# Power_Circuit.net
KiCad netlist of a schematic drawn in Altium Designer
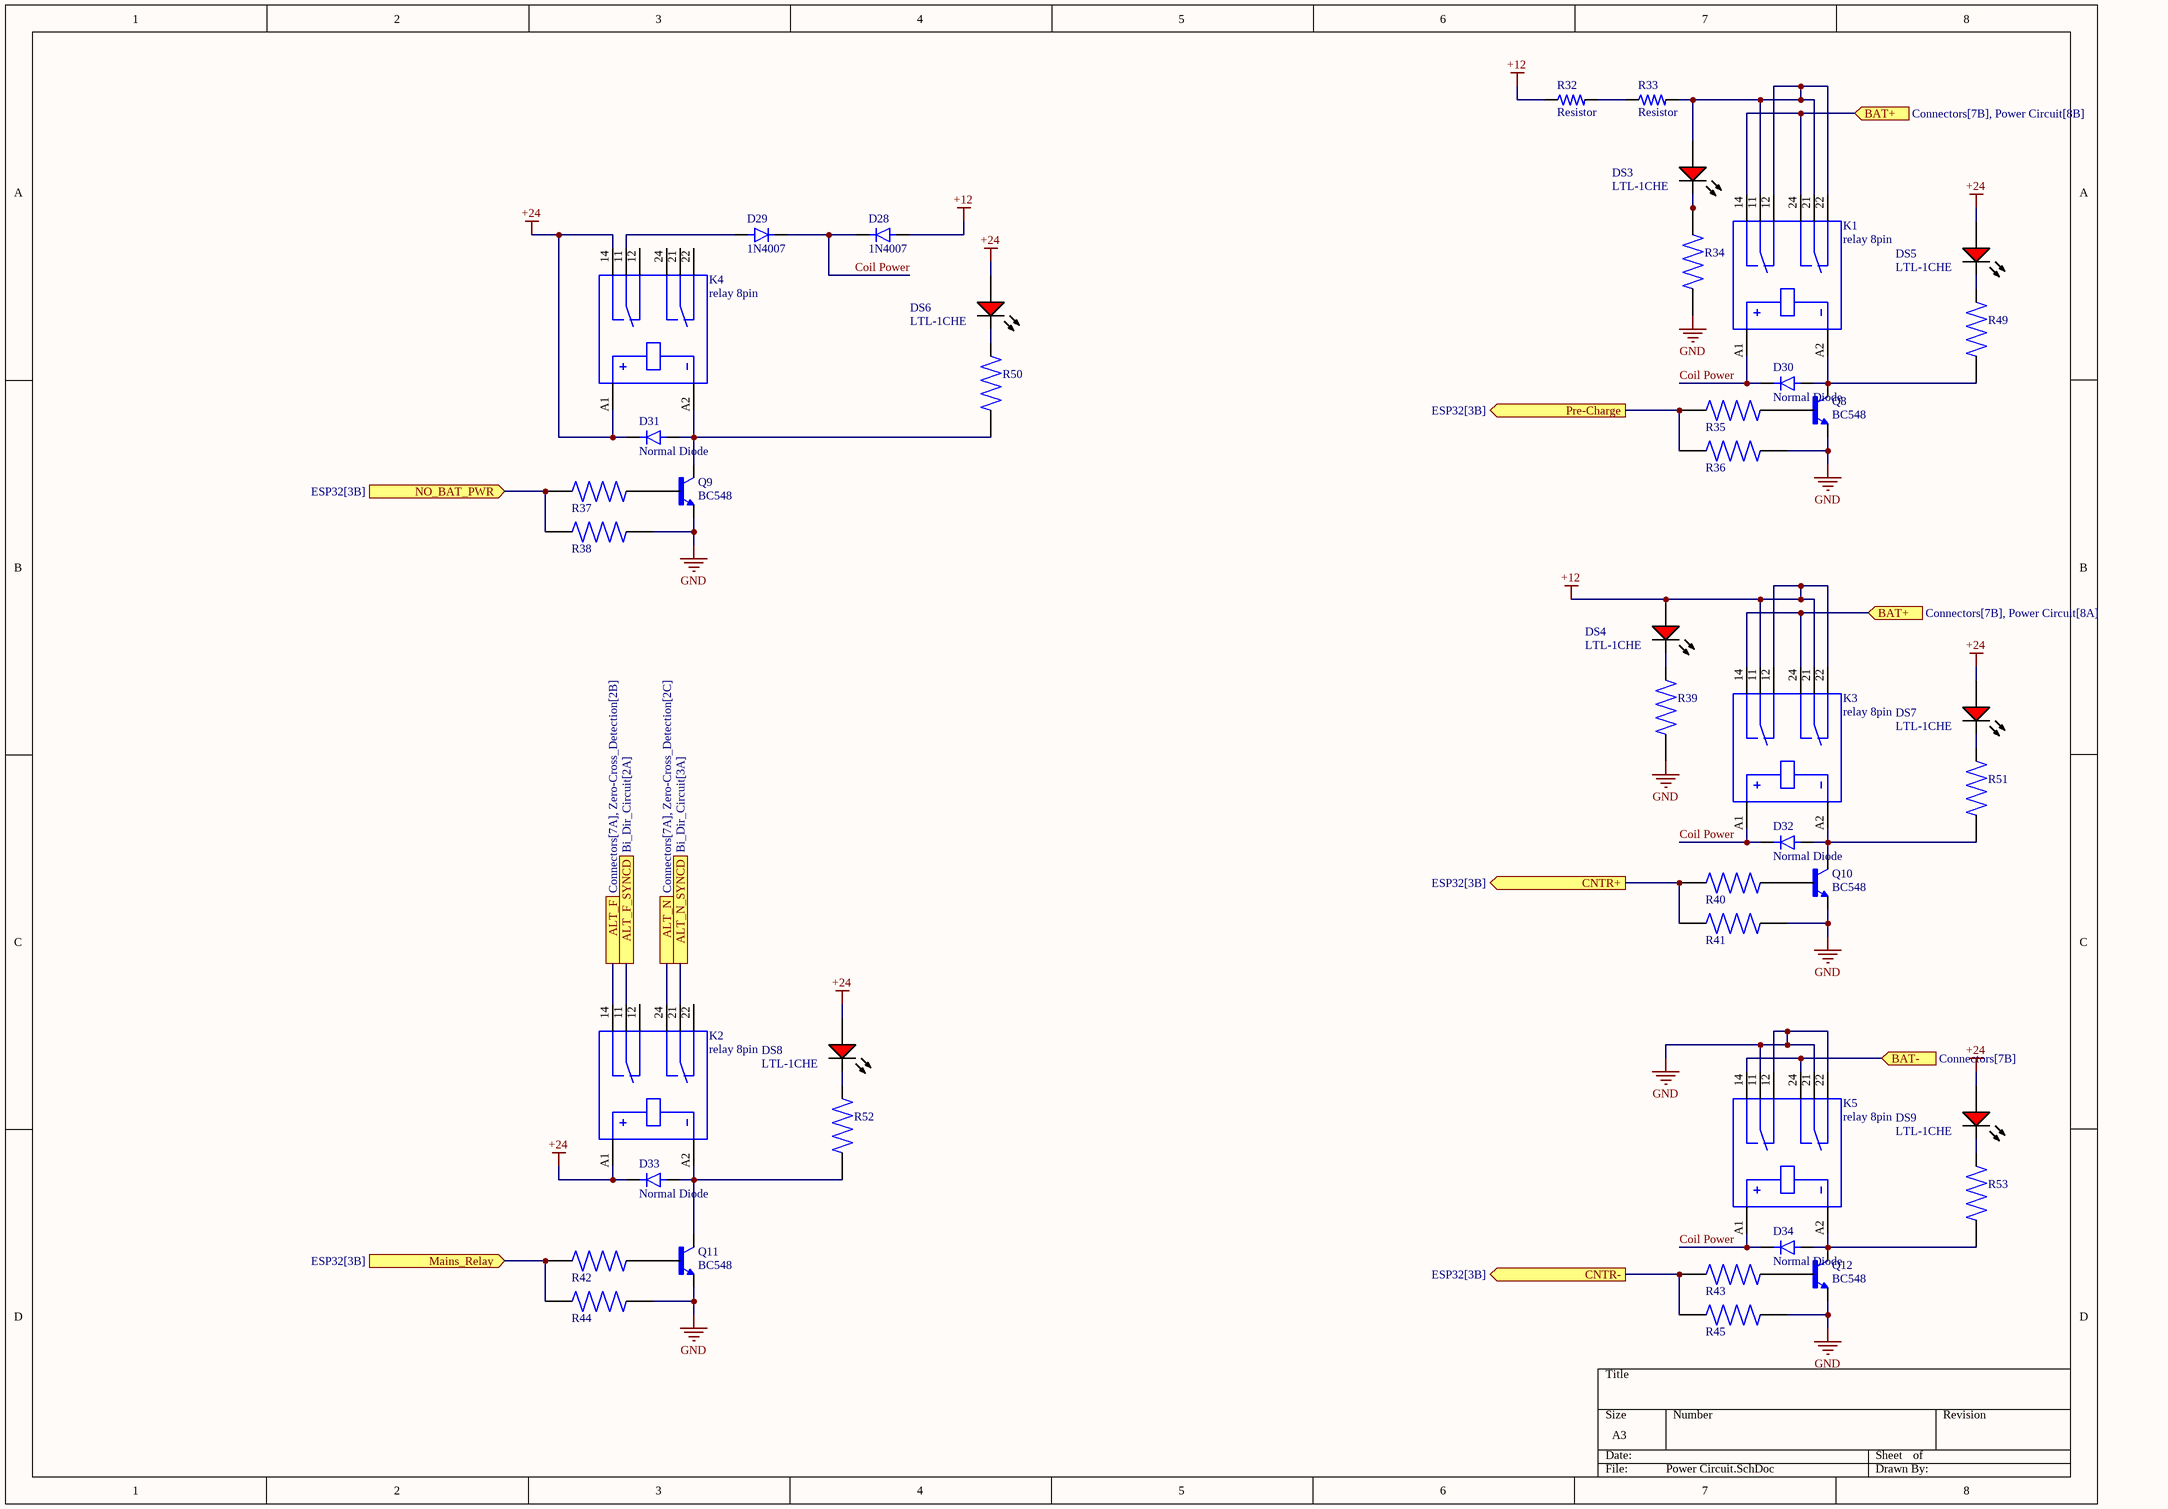
[diagram p0: Power Circuit.SchDoc]

(export (version "E")
  (design (tool "Eeschema 10.0.6"))
  (components
    (comp (ref "D28")
      (value "1N4007")
      (footprint "Common Trhough Hole")
      (fields (field (name "MF") "NTE Electronics, Inc."))
      (libsource (lib "Diodes Through Hole") (part "Normal Diode"))
    )
    (comp (ref "D29")
      (value "1N4007")
      (footprint "Common Trhough Hole")
      (fields (field (name "MF") "NTE Electronics, Inc."))
      (libsource (lib "Diodes Through Hole") (part "Normal Diode"))
    )
    (comp (ref "D30")
      (value "Normal Diode")
      (footprint "Common Trhough Hole")
      (fields (field (name "MF") "NTE Electronics, Inc.") (field (name "MP") "1N4007"))
      (libsource (lib "Diodes Through Hole") (part "Normal Diode"))
    )
    (comp (ref "D31")
      (value "Normal Diode")
      (footprint "Common Trhough Hole")
      (fields (field (name "MF") "NTE Electronics, Inc.") (field (name "MP") "1N4007"))
      (libsource (lib "Diodes Through Hole") (part "Normal Diode"))
    )
    (comp (ref "D32")
      (value "Normal Diode")
      (footprint "Common Trhough Hole")
      (fields (field (name "MF") "NTE Electronics, Inc.") (field (name "MP") "1N4007"))
      (libsource (lib "Diodes Through Hole") (part "Normal Diode"))
    )
    (comp (ref "D33")
      (value "Normal Diode")
      (footprint "Common Trhough Hole")
      (fields (field (name "MF") "NTE Electronics, Inc.") (field (name "MP") "1N4007"))
      (libsource (lib "Diodes Through Hole") (part "Normal Diode"))
    )
    (comp (ref "D34")
      (value "Normal Diode")
      (footprint "Common Trhough Hole")
      (fields (field (name "MF") "NTE Electronics, Inc.") (field (name "MP") "1N4007"))
      (libsource (lib "Diodes Through Hole") (part "Normal Diode"))
    )
    (comp (ref "DS3")
      (value "LTL-1CHE")
      (footprint "LED3mm")
      (description "Radial LED, 12.6 mcd, 20 mA, 2 V, -55 to 100 degC, 2-Pin THD, RoHS, Bulk")
      (fields (field (name "TOLERANCE") "20%"))
      (libsource (lib "MySCH_Library") (part "RED_LED 3mm"))
    )
    (comp (ref "DS4")
      (value "LTL-1CHE")
      (footprint "LED3mm")
      (description "Radial LED, 12.6 mcd, 20 mA, 2 V, -55 to 100 degC, 2-Pin THD, RoHS, Bulk")
      (fields (field (name "TOLERANCE") "20%"))
      (libsource (lib "MySCH_Library") (part "RED_LED 3mm"))
    )
    (comp (ref "DS5")
      (value "LTL-1CHE")
      (footprint "LED3mm")
      (description "Radial LED, 12.6 mcd, 20 mA, 2 V, -55 to 100 degC, 2-Pin THD, RoHS, Bulk")
      (fields (field (name "TOLERANCE") "20%"))
      (libsource (lib "MySCH_Library") (part "RED_LED 3mm"))
    )
    (comp (ref "DS6")
      (value "LTL-1CHE")
      (footprint "LED3mm")
      (description "Radial LED, 12.6 mcd, 20 mA, 2 V, -55 to 100 degC, 2-Pin THD, RoHS, Bulk")
      (fields (field (name "TOLERANCE") "20%"))
      (libsource (lib "MySCH_Library") (part "RED_LED 3mm"))
    )
    (comp (ref "DS7")
      (value "LTL-1CHE")
      (footprint "LED3mm")
      (description "Radial LED, 12.6 mcd, 20 mA, 2 V, -55 to 100 degC, 2-Pin THD, RoHS, Bulk")
      (fields (field (name "TOLERANCE") "20%"))
      (libsource (lib "MySCH_Library") (part "RED_LED 3mm"))
    )
    (comp (ref "DS8")
      (value "LTL-1CHE")
      (footprint "LED3mm")
      (description "Radial LED, 12.6 mcd, 20 mA, 2 V, -55 to 100 degC, 2-Pin THD, RoHS, Bulk")
      (fields (field (name "TOLERANCE") "20%"))
      (libsource (lib "MySCH_Library") (part "RED_LED 3mm"))
    )
    (comp (ref "DS9")
      (value "LTL-1CHE")
      (footprint "LED3mm")
      (description "Radial LED, 12.6 mcd, 20 mA, 2 V, -55 to 100 degC, 2-Pin THD, RoHS, Bulk")
      (fields (field (name "TOLERANCE") "20%"))
      (libsource (lib "MySCH_Library") (part "RED_LED 3mm"))
    )
    (comp (ref "K1")
      (value "relay 8pin")
      (footprint "Relay socket 8pin")
      (description "General Purpose Relay DPDT _2 Form C_ 24VDC Coil Through Hole")
      (fields (field (name "MF") "TE Connectivity") (field (name "MP") "1-1393243-0"))
      (libsource (lib "MySCH_Library") (part "relay 8pin"))
    )
    (comp (ref "K2")
      (value "relay 8pin")
      (footprint "Relay socket 8pin")
      (description "General Purpose Relay DPDT _2 Form C_ 24VDC Coil Through Hole")
      (fields (field (name "MF") "TE Connectivity") (field (name "MP") "1-1393243-0"))
      (libsource (lib "MySCH_Library") (part "relay 8pin"))
    )
    (comp (ref "K3")
      (value "relay 8pin")
      (footprint "Relay socket 8pin")
      (description "General Purpose Relay DPDT _2 Form C_ 24VDC Coil Through Hole")
      (fields (field (name "MF") "TE Connectivity") (field (name "MP") "1-1393243-0"))
      (libsource (lib "MySCH_Library") (part "relay 8pin"))
    )
    (comp (ref "K4")
      (value "relay 8pin")
      (footprint "Relay socket 8pin")
      (description "General Purpose Relay DPDT _2 Form C_ 24VDC Coil Through Hole")
      (fields (field (name "MF") "TE Connectivity") (field (name "MP") "1-1393243-0"))
      (libsource (lib "MySCH_Library") (part "relay 8pin"))
    )
    (comp (ref "K5")
      (value "relay 8pin")
      (footprint "Relay socket 8pin")
      (description "General Purpose Relay DPDT _2 Form C_ 24VDC Coil Through Hole")
      (fields (field (name "MF") "TE Connectivity") (field (name "MP") "1-1393243-0"))
      (libsource (lib "MySCH_Library") (part "relay 8pin"))
    )
    (comp (ref "Q8")
      (value "BC548")
      (footprint "bc548")
      (description "Bipolar (BJT) Transistor NPN 30V 100mA 300MHz 500mW Through Hole TO-92-3")
      (fields (field (name "MF") "ON Semiconductor"))
      (libsource (lib "MySCH_Library") (part "BC548"))
    )
    (comp (ref "Q9")
      (value "BC548")
      (footprint "bc548")
      (description "Bipolar (BJT) Transistor NPN 30V 100mA 300MHz 500mW Through Hole TO-92-3")
      (fields (field (name "MF") "ON Semiconductor"))
      (libsource (lib "MySCH_Library") (part "BC548"))
    )
    (comp (ref "Q10")
      (value "BC548")
      (footprint "bc548")
      (description "Bipolar (BJT) Transistor NPN 30V 100mA 300MHz 500mW Through Hole TO-92-3")
      (fields (field (name "MF") "ON Semiconductor"))
      (libsource (lib "MySCH_Library") (part "BC548"))
    )
    (comp (ref "Q11")
      (value "BC548")
      (footprint "bc548")
      (description "Bipolar (BJT) Transistor NPN 30V 100mA 300MHz 500mW Through Hole TO-92-3")
      (fields (field (name "MF") "ON Semiconductor"))
      (libsource (lib "MySCH_Library") (part "BC548"))
    )
    (comp (ref "Q12")
      (value "BC548")
      (footprint "bc548")
      (description "Bipolar (BJT) Transistor NPN 30V 100mA 300MHz 500mW Through Hole TO-92-3")
      (fields (field (name "MF") "ON Semiconductor"))
      (libsource (lib "MySCH_Library") (part "BC548"))
    )
    (comp (ref "R32")
      (value "Resistor")
      (footprint "Resistor_Through Hole")
      (fields
        (field (name "MP") "2-2176053-0")
        (field (name "TOLERANCE") "1%")
        (field (name "MF") "TE Connectivity")
      )
      (libsource (lib "Resistors Through Hole") (part "Resistor"))
    )
    (comp (ref "R33")
      (value "Resistor")
      (footprint "Resistor_Through Hole")
      (fields
        (field (name "MP") "2-2176053-0")
        (field (name "TOLERANCE") "1%")
        (field (name "MF") "TE Connectivity")
      )
      (libsource (lib "Resistors Through Hole") (part "Resistor"))
    )
    (comp (ref "R34")
      (value "Resistor_Through Hole")
      (footprint "Resistor_Through Hole")
      (description "1.02 Ohms Â±1% 0.25W, 1/4W Through Hole Resistor Axial Metal Film")
      (fields (field (name "MP") "MFR-25FTE52-1R") (field (name "MF") "Yageo"))
      (libsource (lib "MySCH_Library") (part "Resistor_Through Hole"))
    )
    (comp (ref "R35")
      (value "Resistor_Through Hole")
      (footprint "Resistor_Through Hole")
      (description "1.02 Ohms Â±1% 0.25W, 1/4W Through Hole Resistor Axial Metal Film")
      (fields (field (name "MP") "MFR-25FTE52-1R") (field (name "MF") "Yageo"))
      (libsource (lib "MySCH_Library") (part "Resistor_Through Hole"))
    )
    (comp (ref "R36")
      (value "Resistor_Through Hole")
      (footprint "Resistor_Through Hole")
      (description "1.02 Ohms Â±1% 0.25W, 1/4W Through Hole Resistor Axial Metal Film")
      (fields (field (name "MP") "MFR-25FTE52-1R") (field (name "MF") "Yageo"))
      (libsource (lib "MySCH_Library") (part "Resistor_Through Hole"))
    )
    (comp (ref "R37")
      (value "Resistor_Through Hole")
      (footprint "Resistor_Through Hole")
      (description "1.02 Ohms Â±1% 0.25W, 1/4W Through Hole Resistor Axial Metal Film")
      (fields (field (name "MP") "MFR-25FTE52-1R") (field (name "MF") "Yageo"))
      (libsource (lib "MySCH_Library") (part "Resistor_Through Hole"))
    )
    (comp (ref "R38")
      (value "Resistor_Through Hole")
      (footprint "Resistor_Through Hole")
      (description "1.02 Ohms Â±1% 0.25W, 1/4W Through Hole Resistor Axial Metal Film")
      (fields (field (name "MP") "MFR-25FTE52-1R") (field (name "MF") "Yageo"))
      (libsource (lib "MySCH_Library") (part "Resistor_Through Hole"))
    )
    (comp (ref "R39")
      (value "Resistor_Through Hole")
      (footprint "Resistor_Through Hole")
      (description "1.02 Ohms Â±1% 0.25W, 1/4W Through Hole Resistor Axial Metal Film")
      (fields (field (name "MP") "MFR-25FTE52-1R") (field (name "MF") "Yageo"))
      (libsource (lib "MySCH_Library") (part "Resistor_Through Hole"))
    )
    (comp (ref "R40")
      (value "Resistor_Through Hole")
      (footprint "Resistor_Through Hole")
      (description "1.02 Ohms Â±1% 0.25W, 1/4W Through Hole Resistor Axial Metal Film")
      (fields (field (name "MP") "MFR-25FTE52-1R") (field (name "MF") "Yageo"))
      (libsource (lib "MySCH_Library") (part "Resistor_Through Hole"))
    )
    (comp (ref "R41")
      (value "Resistor_Through Hole")
      (footprint "Resistor_Through Hole")
      (description "1.02 Ohms Â±1% 0.25W, 1/4W Through Hole Resistor Axial Metal Film")
      (fields (field (name "MP") "MFR-25FTE52-1R") (field (name "MF") "Yageo"))
      (libsource (lib "MySCH_Library") (part "Resistor_Through Hole"))
    )
    (comp (ref "R42")
      (value "Resistor_Through Hole")
      (footprint "Resistor_Through Hole")
      (description "1.02 Ohms Â±1% 0.25W, 1/4W Through Hole Resistor Axial Metal Film")
      (fields (field (name "MP") "MFR-25FTE52-1R") (field (name "MF") "Yageo"))
      (libsource (lib "MySCH_Library") (part "Resistor_Through Hole"))
    )
    (comp (ref "R43")
      (value "Resistor_Through Hole")
      (footprint "Resistor_Through Hole")
      (description "1.02 Ohms Â±1% 0.25W, 1/4W Through Hole Resistor Axial Metal Film")
      (fields (field (name "MP") "MFR-25FTE52-1R") (field (name "MF") "Yageo"))
      (libsource (lib "MySCH_Library") (part "Resistor_Through Hole"))
    )
    (comp (ref "R44")
      (value "Resistor_Through Hole")
      (footprint "Resistor_Through Hole")
      (description "1.02 Ohms Â±1% 0.25W, 1/4W Through Hole Resistor Axial Metal Film")
      (fields (field (name "MP") "MFR-25FTE52-1R") (field (name "MF") "Yageo"))
      (libsource (lib "MySCH_Library") (part "Resistor_Through Hole"))
    )
    (comp (ref "R45")
      (value "Resistor_Through Hole")
      (footprint "Resistor_Through Hole")
      (description "1.02 Ohms Â±1% 0.25W, 1/4W Through Hole Resistor Axial Metal Film")
      (fields (field (name "MP") "MFR-25FTE52-1R") (field (name "MF") "Yageo"))
      (libsource (lib "MySCH_Library") (part "Resistor_Through Hole"))
    )
    (comp (ref "R49")
      (value "Resistor_Through Hole")
      (footprint "Resistor_Through Hole")
      (description "1.02 Ohms Â±1% 0.25W, 1/4W Through Hole Resistor Axial Metal Film")
      (fields (field (name "MP") "MFR-25FTE52-1R") (field (name "MF") "Yageo"))
      (libsource (lib "MySCH_Library") (part "Resistor_Through Hole"))
    )
    (comp (ref "R50")
      (value "Resistor_Through Hole")
      (footprint "Resistor_Through Hole")
      (description "1.02 Ohms Â±1% 0.25W, 1/4W Through Hole Resistor Axial Metal Film")
      (fields (field (name "MP") "MFR-25FTE52-1R") (field (name "MF") "Yageo"))
      (libsource (lib "MySCH_Library") (part "Resistor_Through Hole"))
    )
    (comp (ref "R51")
      (value "Resistor_Through Hole")
      (footprint "Resistor_Through Hole")
      (description "1.02 Ohms Â±1% 0.25W, 1/4W Through Hole Resistor Axial Metal Film")
      (fields (field (name "MP") "MFR-25FTE52-1R") (field (name "MF") "Yageo"))
      (libsource (lib "MySCH_Library") (part "Resistor_Through Hole"))
    )
    (comp (ref "R52")
      (value "Resistor_Through Hole")
      (footprint "Resistor_Through Hole")
      (description "1.02 Ohms Â±1% 0.25W, 1/4W Through Hole Resistor Axial Metal Film")
      (fields (field (name "MP") "MFR-25FTE52-1R") (field (name "MF") "Yageo"))
      (libsource (lib "MySCH_Library") (part "Resistor_Through Hole"))
    )
    (comp (ref "R53")
      (value "Resistor_Through Hole")
      (footprint "Resistor_Through Hole")
      (description "1.02 Ohms Â±1% 0.25W, 1/4W Through Hole Resistor Axial Metal Film")
      (fields (field (name "MP") "MFR-25FTE52-1R") (field (name "MF") "Yageo"))
      (libsource (lib "MySCH_Library") (part "Resistor_Through Hole"))
    )
  )
  (nets
    (net (code "1") (name "+12") (class "Default")
      (node (ref "D28") (pin "2") (pinfunction "A_2") (pintype "passive"))
      (node (ref "DS4") (pin "1") (pinfunction "A_1") (pintype "passive"))
      (node (ref "K3") (pin "11") (pinfunction "6_11") (pintype "passive"))
      (node (ref "K3") (pin "12") (pinfunction "7_12") (pintype "passive"))
      (node (ref "K3") (pin "21") (pinfunction "3_21") (pintype "passive"))
      (node (ref "K3") (pin "22") (pinfunction "2_22") (pintype "passive"))
      (node (ref "R32") (pin "1") (pinfunction "1_1") (pintype "passive"))
    )
    (net (code "2") (name "+24") (class "Default")
      (node (ref "D31") (pin "1") (pinfunction "K_1") (pintype "passive"))
      (node (ref "D33") (pin "1") (pinfunction "K_1") (pintype "passive"))
      (node (ref "DS5") (pin "1") (pinfunction "A_1") (pintype "passive"))
      (node (ref "DS6") (pin "1") (pinfunction "A_1") (pintype "passive"))
      (node (ref "DS7") (pin "1") (pinfunction "A_1") (pintype "passive"))
      (node (ref "DS8") (pin "1") (pinfunction "A_1") (pintype "passive"))
      (node (ref "DS9") (pin "1") (pinfunction "A_1") (pintype "passive"))
      (node (ref "K2") (pin "A1") (pinfunction "1_A1") (pintype "passive"))
      (node (ref "K4") (pin "14") (pinfunction "5_14") (pintype "passive"))
      (node (ref "K4") (pin "A1") (pinfunction "1_A1") (pintype "passive"))
    )
    (net (code "3") (name "/ALT_F") (class "Default")
      (node (ref "K2") (pin "14") (pinfunction "5_14") (pintype "passive"))
    )
    (net (code "4") (name "/ALT_F_SYNCD") (class "Default")
      (node (ref "K2") (pin "11") (pinfunction "6_11") (pintype "passive"))
    )
    (net (code "5") (name "/ALT_N") (class "Default")
      (node (ref "K2") (pin "24") (pinfunction "4_24") (pintype "passive"))
    )
    (net (code "6") (name "/ALT_N_SYNCD") (class "Default")
      (node (ref "K2") (pin "21") (pinfunction "3_21") (pintype "passive"))
    )
    (net (code "7") (name "/BAT+") (class "Default")
      (node (ref "K1") (pin "14") (pinfunction "5_14") (pintype "passive"))
      (node (ref "K1") (pin "24") (pinfunction "4_24") (pintype "passive"))
      (node (ref "K3") (pin "14") (pinfunction "5_14") (pintype "passive"))
      (node (ref "K3") (pin "24") (pinfunction "4_24") (pintype "passive"))
    )
    (net (code "8") (name "/BAT-") (class "Default")
      (node (ref "K5") (pin "14") (pinfunction "5_14") (pintype "passive"))
      (node (ref "K5") (pin "24") (pinfunction "4_24") (pintype "passive"))
    )
    (net (code "9") (name "/CNTR+") (class "Default")
      (node (ref "R40") (pin "2") (pinfunction "2_2") (pintype "passive"))
      (node (ref "R41") (pin "2") (pinfunction "2_2") (pintype "passive"))
    )
    (net (code "10") (name "/CNTR-") (class "Default")
      (node (ref "R43") (pin "2") (pinfunction "2_2") (pintype "passive"))
      (node (ref "R45") (pin "2") (pinfunction "2_2") (pintype "passive"))
    )
    (net (code "11") (name "/Coil Power") (class "Default")
      (node (ref "D28") (pin "1") (pinfunction "K_1") (pintype "passive"))
      (node (ref "D29") (pin "1") (pinfunction "K_1") (pintype "passive"))
      (node (ref "D30") (pin "1") (pinfunction "K_1") (pintype "passive"))
      (node (ref "D32") (pin "1") (pinfunction "K_1") (pintype "passive"))
      (node (ref "D34") (pin "1") (pinfunction "K_1") (pintype "passive"))
      (node (ref "K1") (pin "A1") (pinfunction "1_A1") (pintype "passive"))
      (node (ref "K3") (pin "A1") (pinfunction "1_A1") (pintype "passive"))
      (node (ref "K5") (pin "A1") (pinfunction "1_A1") (pintype "passive"))
    )
    (net (code "12") (name "/Mains_Relay") (class "Default")
      (node (ref "R42") (pin "2") (pinfunction "2_2") (pintype "passive"))
      (node (ref "R44") (pin "2") (pinfunction "2_2") (pintype "passive"))
    )
    (net (code "13") (name "/NO_BAT_PWR") (class "Default")
      (node (ref "R37") (pin "2") (pinfunction "2_2") (pintype "passive"))
      (node (ref "R38") (pin "2") (pinfunction "2_2") (pintype "passive"))
    )
    (net (code "14") (name "/Pre-Charge") (class "Default")
      (node (ref "R35") (pin "2") (pinfunction "2_2") (pintype "passive"))
      (node (ref "R36") (pin "2") (pinfunction "2_2") (pintype "passive"))
    )
    (net (code "15") (name "GND") (class "Default")
      (node (ref "K5") (pin "11") (pinfunction "6_11") (pintype "passive"))
      (node (ref "K5") (pin "12") (pinfunction "7_12") (pintype "passive"))
      (node (ref "K5") (pin "21") (pinfunction "3_21") (pintype "passive"))
      (node (ref "K5") (pin "22") (pinfunction "2_22") (pintype "passive"))
      (node (ref "Q10") (pin "3") (pinfunction "E_3") (pintype "passive"))
      (node (ref "Q11") (pin "3") (pinfunction "E_3") (pintype "passive"))
      (node (ref "Q12") (pin "3") (pinfunction "E_3") (pintype "passive"))
      (node (ref "Q8") (pin "3") (pinfunction "E_3") (pintype "passive"))
      (node (ref "Q9") (pin "3") (pinfunction "E_3") (pintype "passive"))
      (node (ref "R34") (pin "2") (pinfunction "2_2") (pintype "passive"))
      (node (ref "R36") (pin "1") (pinfunction "1_1") (pintype "passive"))
      (node (ref "R38") (pin "1") (pinfunction "1_1") (pintype "passive"))
      (node (ref "R39") (pin "2") (pinfunction "2_2") (pintype "passive"))
      (node (ref "R41") (pin "1") (pinfunction "1_1") (pintype "passive"))
      (node (ref "R44") (pin "1") (pinfunction "1_1") (pintype "passive"))
      (node (ref "R45") (pin "1") (pinfunction "1_1") (pintype "passive"))
    )
    (net (code "16") (name "Net-(D29-A)") (class "Default")
      (node (ref "D29") (pin "2") (pinfunction "A_2") (pintype "passive"))
      (node (ref "K4") (pin "11") (pinfunction "6_11") (pintype "passive"))
    )
    (net (code "17") (name "Net-(D30-A)") (class "Default")
      (node (ref "D30") (pin "2") (pinfunction "A_2") (pintype "passive"))
      (node (ref "K1") (pin "A2") (pinfunction "8_A2") (pintype "passive"))
      (node (ref "Q8") (pin "1") (pinfunction "C_1") (pintype "passive"))
      (node (ref "R49") (pin "2") (pinfunction "2_2") (pintype "passive"))
    )
    (net (code "18") (name "Net-(D31-A)") (class "Default")
      (node (ref "D31") (pin "2") (pinfunction "A_2") (pintype "passive"))
      (node (ref "K4") (pin "A2") (pinfunction "8_A2") (pintype "passive"))
      (node (ref "Q9") (pin "1") (pinfunction "C_1") (pintype "passive"))
      (node (ref "R50") (pin "2") (pinfunction "2_2") (pintype "passive"))
    )
    (net (code "19") (name "Net-(D32-A)") (class "Default")
      (node (ref "D32") (pin "2") (pinfunction "A_2") (pintype "passive"))
      (node (ref "K3") (pin "A2") (pinfunction "8_A2") (pintype "passive"))
      (node (ref "Q10") (pin "1") (pinfunction "C_1") (pintype "passive"))
      (node (ref "R51") (pin "2") (pinfunction "2_2") (pintype "passive"))
    )
    (net (code "20") (name "Net-(D33-A)") (class "Default")
      (node (ref "D33") (pin "2") (pinfunction "A_2") (pintype "passive"))
      (node (ref "K2") (pin "A2") (pinfunction "8_A2") (pintype "passive"))
      (node (ref "Q11") (pin "1") (pinfunction "C_1") (pintype "passive"))
      (node (ref "R52") (pin "2") (pinfunction "2_2") (pintype "passive"))
    )
    (net (code "21") (name "Net-(D34-A)") (class "Default")
      (node (ref "D34") (pin "2") (pinfunction "A_2") (pintype "passive"))
      (node (ref "K5") (pin "A2") (pinfunction "8_A2") (pintype "passive"))
      (node (ref "Q12") (pin "1") (pinfunction "C_1") (pintype "passive"))
      (node (ref "R53") (pin "2") (pinfunction "2_2") (pintype "passive"))
    )
    (net (code "22") (name "Net-(DS3-A)") (class "Default")
      (node (ref "DS3") (pin "1") (pinfunction "A_1") (pintype "passive"))
      (node (ref "K1") (pin "11") (pinfunction "6_11") (pintype "passive"))
      (node (ref "K1") (pin "12") (pinfunction "7_12") (pintype "passive"))
      (node (ref "K1") (pin "21") (pinfunction "3_21") (pintype "passive"))
      (node (ref "K1") (pin "22") (pinfunction "2_22") (pintype "passive"))
      (node (ref "R33") (pin "2") (pinfunction "2_2") (pintype "passive"))
    )
    (net (code "23") (name "Net-(DS3-K)") (class "Default")
      (node (ref "DS3") (pin "2") (pinfunction "K_2") (pintype "passive"))
      (node (ref "R34") (pin "1") (pinfunction "1_1") (pintype "passive"))
    )
    (net (code "24") (name "Net-(DS4-K)") (class "Default")
      (node (ref "DS4") (pin "2") (pinfunction "K_2") (pintype "passive"))
      (node (ref "R39") (pin "1") (pinfunction "1_1") (pintype "passive"))
    )
    (net (code "25") (name "Net-(DS5-K)") (class "Default")
      (node (ref "DS5") (pin "2") (pinfunction "K_2") (pintype "passive"))
      (node (ref "R49") (pin "1") (pinfunction "1_1") (pintype "passive"))
    )
    (net (code "26") (name "Net-(DS6-K)") (class "Default")
      (node (ref "DS6") (pin "2") (pinfunction "K_2") (pintype "passive"))
      (node (ref "R50") (pin "1") (pinfunction "1_1") (pintype "passive"))
    )
    (net (code "27") (name "Net-(DS7-K)") (class "Default")
      (node (ref "DS7") (pin "2") (pinfunction "K_2") (pintype "passive"))
      (node (ref "R51") (pin "1") (pinfunction "1_1") (pintype "passive"))
    )
    (net (code "28") (name "Net-(DS8-K)") (class "Default")
      (node (ref "DS8") (pin "2") (pinfunction "K_2") (pintype "passive"))
      (node (ref "R52") (pin "1") (pinfunction "1_1") (pintype "passive"))
    )
    (net (code "29") (name "Net-(DS9-K)") (class "Default")
      (node (ref "DS9") (pin "2") (pinfunction "K_2") (pintype "passive"))
      (node (ref "R53") (pin "1") (pinfunction "1_1") (pintype "passive"))
    )
    (net (code "30") (name "Net-(Q8-B)") (class "Default")
      (node (ref "Q8") (pin "2") (pinfunction "B_2") (pintype "passive"))
      (node (ref "R35") (pin "1") (pinfunction "1_1") (pintype "passive"))
    )
    (net (code "31") (name "Net-(Q9-B)") (class "Default")
      (node (ref "Q9") (pin "2") (pinfunction "B_2") (pintype "passive"))
      (node (ref "R37") (pin "1") (pinfunction "1_1") (pintype "passive"))
    )
    (net (code "32") (name "Net-(Q10-B)") (class "Default")
      (node (ref "Q10") (pin "2") (pinfunction "B_2") (pintype "passive"))
      (node (ref "R40") (pin "1") (pinfunction "1_1") (pintype "passive"))
    )
    (net (code "33") (name "Net-(Q11-B)") (class "Default")
      (node (ref "Q11") (pin "2") (pinfunction "B_2") (pintype "passive"))
      (node (ref "R42") (pin "1") (pinfunction "1_1") (pintype "passive"))
    )
    (net (code "34") (name "Net-(Q12-B)") (class "Default")
      (node (ref "Q12") (pin "2") (pinfunction "B_2") (pintype "passive"))
      (node (ref "R43") (pin "1") (pinfunction "1_1") (pintype "passive"))
    )
    (net (code "35") (name "Net-(R32-Pad2)") (class "Default")
      (node (ref "R32") (pin "2") (pinfunction "2_2") (pintype "passive"))
      (node (ref "R33") (pin "1") (pinfunction "1_1") (pintype "passive"))
    )
    (net (code "36") (name "unconnected-(K2-2-Pad22)") (class "Default")
      (node (ref "K2") (pin "22") (pinfunction "2_22") (pintype "passive"))
    )
    (net (code "37") (name "unconnected-(K2-7-Pad12)") (class "Default")
      (node (ref "K2") (pin "12") (pinfunction "7_12") (pintype "passive"))
    )
    (net (code "38") (name "unconnected-(K4-2-Pad22)") (class "Default")
      (node (ref "K4") (pin "22") (pinfunction "2_22") (pintype "passive"))
    )
    (net (code "39") (name "unconnected-(K4-3-Pad21)") (class "Default")
      (node (ref "K4") (pin "21") (pinfunction "3_21") (pintype "passive"))
    )
    (net (code "40") (name "unconnected-(K4-4-Pad24)") (class "Default")
      (node (ref "K4") (pin "24") (pinfunction "4_24") (pintype "passive"))
    )
    (net (code "41") (name "unconnected-(K4-7-Pad12)") (class "Default")
      (node (ref "K4") (pin "12") (pinfunction "7_12") (pintype "passive"))
    )
  )
)
